# RS_IF.net
KiCad netlist of a schematic drawn in Altium Designer
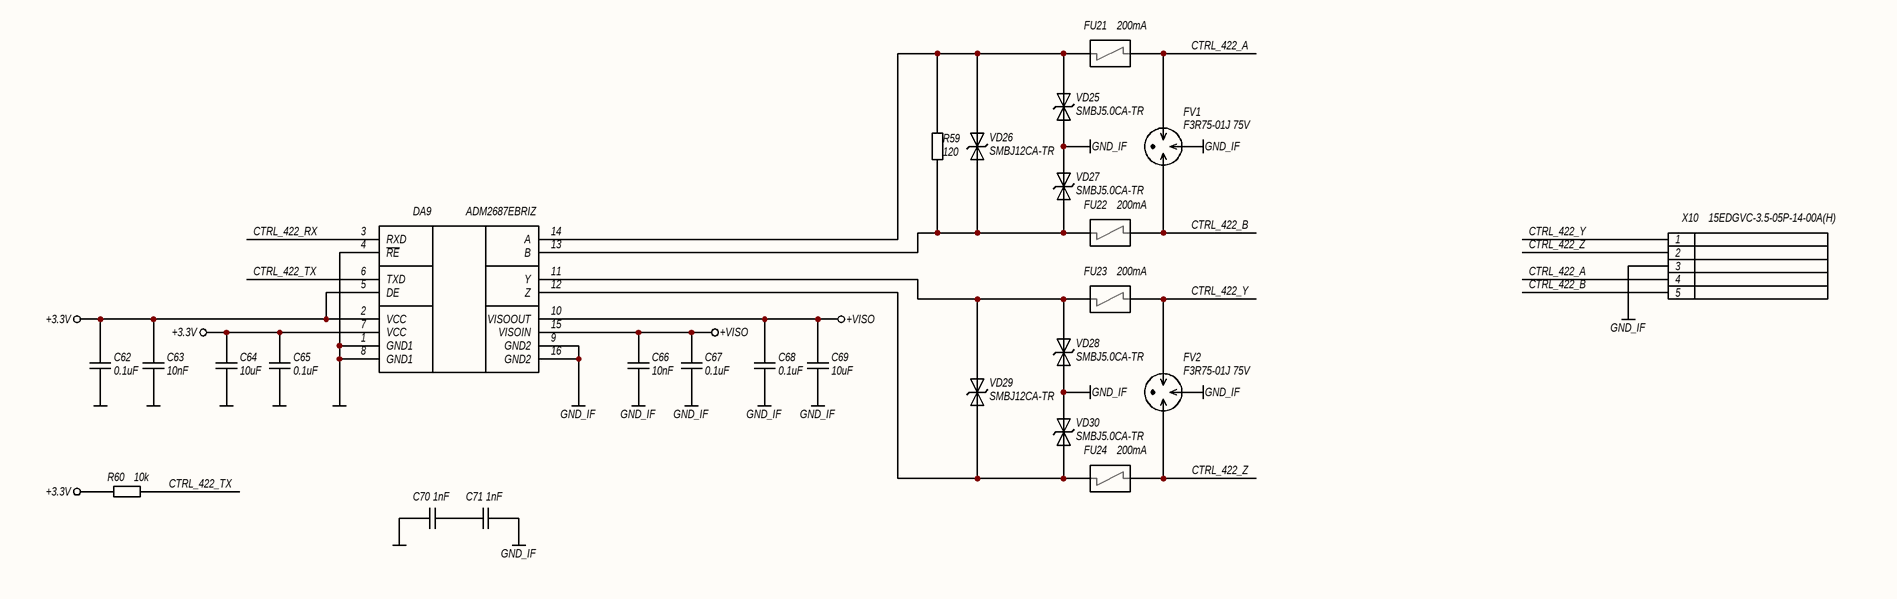
[diagram p0: RS_IF.SchDoc]

(export (version "E")
  (design (tool "Eeschema 10.0.6"))
  (components
    (comp (ref "C62")
      (value "0.1uF")
      (footprint "C0603N")
      (description "Конденсатор")
      (libsource (lib "Components Library") (part "CAP_FIXED"))
    )
    (comp (ref "C63")
      (value "10nF")
      (footprint "C0603N")
      (description "Конденсатор")
      (libsource (lib "Components Library") (part "CAP_FIXED"))
    )
    (comp (ref "C64")
      (value "10uF")
      (footprint "C0805N")
      (description "Конденсатор")
      (libsource (lib "Components Library") (part "CAP_FIXED"))
    )
    (comp (ref "C65")
      (value "0.1uF")
      (footprint "C0603N")
      (description "Конденсатор")
      (libsource (lib "Components Library") (part "CAP_FIXED"))
    )
    (comp (ref "C66")
      (value "10nF")
      (footprint "C0603N")
      (description "Конденсатор")
      (libsource (lib "Components Library") (part "CAP_FIXED"))
    )
    (comp (ref "C67")
      (value "0.1uF")
      (footprint "C0603N")
      (description "Конденсатор")
      (libsource (lib "Components Library") (part "CAP_FIXED"))
    )
    (comp (ref "C68")
      (value "0.1uF")
      (footprint "C0603N")
      (description "Конденсатор")
      (libsource (lib "Components Library") (part "CAP_FIXED"))
    )
    (comp (ref "C69")
      (value "10uF")
      (footprint "C0805N")
      (description "Конденсатор")
      (libsource (lib "Components Library") (part "CAP_FIXED"))
    )
    (comp (ref "C70")
      (value "1nF")
      (footprint "C1808N")
      (description "Конденсатор")
      (libsource (lib "Components Library") (part "CAP_FIXED"))
    )
    (comp (ref "C71")
      (value "1nF")
      (footprint "C1808N")
      (description "Конденсатор")
      (libsource (lib "Components Library") (part "CAP_FIXED"))
    )
    (comp (ref "DA9")
      (value "ADM2687EBRIZ")
      (footprint "SOIC16_IC")
      (description "Микросхема интерфейса RS485")
      (libsource (lib "Components Library") (part "ADM2687E"))
    )
    (comp (ref "FU21")
      (value "200mA")
      (footprint "TBU-CA")
      (description "Полупроводниковый предохранитель")
      (libsource (lib "Components Library") (part "FUSE_TBU"))
    )
    (comp (ref "FU22")
      (value "200mA")
      (footprint "TBU-CA")
      (description "Полупроводниковый предохранитель")
      (libsource (lib "Components Library") (part "FUSE_TBU"))
    )
    (comp (ref "FU23")
      (value "200mA")
      (footprint "TBU-CA")
      (description "Полупроводниковый предохранитель")
      (libsource (lib "Components Library") (part "FUSE_TBU"))
    )
    (comp (ref "FU24")
      (value "200mA")
      (footprint "TBU-CA")
      (description "Полупроводниковый предохранитель")
      (libsource (lib "Components Library") (part "FUSE_TBU"))
    )
    (comp (ref "FV1")
      (value "F3R75-01J 75V")
      (footprint "GDT_3PIN_B2")
      (description "Газовый разрядник, трехвыводный")
      (libsource (lib "Components Library") (part "GDT_3PIN"))
    )
    (comp (ref "FV2")
      (value "F3R75-01J 75V")
      (footprint "GDT_3PIN_B2")
      (description "Газовый разрядник, трехвыводный")
      (libsource (lib "Components Library") (part "GDT_3PIN"))
    )
    (comp (ref "R59")
      (value "120")
      (footprint "R0805N")
      (description "Резистор")
      (libsource (lib "") (part "RES_FIXED_1"))
    )
    (comp (ref "R60")
      (value "10k")
      (footprint "R0603N")
      (description "Резистор")
      (libsource (lib "Components Library") (part "RES_FIXED"))
    )
    (comp (ref "VD25")
      (value "SMBJ5.0CA-TR")
      (footprint "SMB")
      (description "TVS диод двунаправленный")
      (libsource (lib "Components Library") (part "TVS_BIDIR"))
    )
    (comp (ref "VD26")
      (value "SMBJ12CA-TR")
      (footprint "SMB")
      (description "TVS диод двунаправленный")
      (libsource (lib "Components Library") (part "TVS_BIDIR"))
    )
    (comp (ref "VD27")
      (value "SMBJ5.0CA-TR")
      (footprint "SMB")
      (description "TVS диод двунаправленный")
      (libsource (lib "Components Library") (part "TVS_BIDIR"))
    )
    (comp (ref "VD28")
      (value "SMBJ5.0CA-TR")
      (footprint "SMB")
      (description "TVS диод двунаправленный")
      (libsource (lib "Components Library") (part "TVS_BIDIR"))
    )
    (comp (ref "VD29")
      (value "SMBJ12CA-TR")
      (footprint "SMB")
      (description "TVS диод двунаправленный")
      (libsource (lib "Components Library") (part "TVS_BIDIR"))
    )
    (comp (ref "VD30")
      (value "SMBJ5.0CA-TR")
      (footprint "SMB")
      (description "TVS диод двунаправленный")
      (libsource (lib "Components Library") (part "TVS_BIDIR"))
    )
    (comp (ref "X10")
      (value "15EDGVC-3.5-05P-14-00A(H)")
      (footprint "15EDGVC-3.5-05P-14-00A(H)")
      (description "Разъем, 5 контактов")
      (libsource (lib "Components Library") (part "Connector 5"))
    )
  )
  (nets
    (net (code "1") (name "+3.3V") (class "Default")
      (node (ref "C62") (pin "2") (pinfunction "2_2") (pintype "passive"))
      (node (ref "C63") (pin "1") (pinfunction "1_1") (pintype "passive"))
      (node (ref "C64") (pin "2") (pinfunction "2_2") (pintype "passive"))
      (node (ref "C65") (pin "2") (pinfunction "2_2") (pintype "passive"))
      (node (ref "DA9") (pin "2") (pinfunction "VCC_2") (pintype "power_in"))
      (node (ref "DA9") (pin "5") (pinfunction "DE_5") (pintype "power_in"))
      (node (ref "DA9") (pin "7") (pinfunction "VCC_7") (pintype "power_in"))
      (node (ref "R60") (pin "2") (pinfunction "2_2") (pintype "passive"))
    )
    (net (code "2") (name "+VISO") (class "Default")
      (node (ref "C66") (pin "1") (pinfunction "1_1") (pintype "passive"))
      (node (ref "C67") (pin "2") (pinfunction "2_2") (pintype "passive"))
      (node (ref "C68") (pin "2") (pinfunction "2_2") (pintype "passive"))
      (node (ref "C69") (pin "2") (pinfunction "2_2") (pintype "passive"))
      (node (ref "DA9") (pin "10") (pinfunction "VISOOUT_10") (pintype "power_in"))
      (node (ref "DA9") (pin "15") (pinfunction "VISOIN_15") (pintype "power_in"))
    )
    (net (code "3") (name "/CTRL_422_A") (class "Default")
      (node (ref "FU21") (pin "3") (pinfunction "IN/OUT_3") (pintype "passive"))
      (node (ref "FV1") (pin "1") (pinfunction "1_1") (pintype "passive"))
      (node (ref "X10") (pin "4") (pinfunction "4_4") (pintype "power_in"))
    )
    (net (code "4") (name "/CTRL_422_B") (class "Default")
      (node (ref "FU22") (pin "3") (pinfunction "IN/OUT_3") (pintype "passive"))
      (node (ref "FV1") (pin "3") (pinfunction "3_3") (pintype "passive"))
      (node (ref "X10") (pin "5") (pinfunction "5_5") (pintype "power_in"))
    )
    (net (code "5") (name "/CTRL_422_RX") (class "Default")
      (node (ref "DA9") (pin "3") (pinfunction "RXD_3") (pintype "power_in"))
    )
    (net (code "6") (name "/CTRL_422_TX") (class "Default")
      (node (ref "DA9") (pin "6") (pinfunction "TXD_6") (pintype "power_in"))
      (node (ref "R60") (pin "1") (pinfunction "1_1") (pintype "passive"))
    )
    (net (code "7") (name "/CTRL_422_Y") (class "Default")
      (node (ref "FU23") (pin "3") (pinfunction "IN/OUT_3") (pintype "passive"))
      (node (ref "FV2") (pin "1") (pinfunction "1_1") (pintype "passive"))
      (node (ref "X10") (pin "1") (pinfunction "1_1") (pintype "power_in"))
    )
    (net (code "8") (name "/CTRL_422_Z") (class "Default")
      (node (ref "FU24") (pin "3") (pinfunction "IN/OUT_3") (pintype "passive"))
      (node (ref "FV2") (pin "3") (pinfunction "3_3") (pintype "passive"))
      (node (ref "X10") (pin "2") (pinfunction "2_2") (pintype "power_in"))
    )
    (net (code "9") (name "GND") (class "Default")
      (node (ref "C62") (pin "1") (pinfunction "1_1") (pintype "passive"))
      (node (ref "C63") (pin "2") (pinfunction "2_2") (pintype "passive"))
      (node (ref "C64") (pin "1") (pinfunction "1_1") (pintype "passive"))
      (node (ref "C65") (pin "1") (pinfunction "1_1") (pintype "passive"))
      (node (ref "C70") (pin "2") (pinfunction "2_2") (pintype "passive"))
      (node (ref "DA9") (pin "1") (pinfunction "GND1_1") (pintype "power_in"))
      (node (ref "DA9") (pin "4") (pinfunction "~{RE}_4") (pintype "power_in"))
      (node (ref "DA9") (pin "8") (pinfunction "GND1_8") (pintype "power_in"))
    )
    (net (code "10") (name "GND_IF") (class "Default")
      (node (ref "C66") (pin "2") (pinfunction "2_2") (pintype "passive"))
      (node (ref "C67") (pin "1") (pinfunction "1_1") (pintype "passive"))
      (node (ref "C68") (pin "1") (pinfunction "1_1") (pintype "passive"))
      (node (ref "C69") (pin "1") (pinfunction "1_1") (pintype "passive"))
      (node (ref "C71") (pin "1") (pinfunction "1_1") (pintype "passive"))
      (node (ref "DA9") (pin "16") (pinfunction "GND2_16") (pintype "power_in"))
      (node (ref "DA9") (pin "9") (pinfunction "GND2_9") (pintype "power_in"))
      (node (ref "FV1") (pin "2") (pinfunction "2_2") (pintype "passive"))
      (node (ref "FV2") (pin "2") (pinfunction "2_2") (pintype "passive"))
      (node (ref "VD25") (pin "2") (pinfunction "A2_2") (pintype "passive"))
      (node (ref "VD27") (pin "2") (pinfunction "A2_2") (pintype "passive"))
      (node (ref "VD28") (pin "2") (pinfunction "A2_2") (pintype "passive"))
      (node (ref "VD30") (pin "2") (pinfunction "A2_2") (pintype "passive"))
      (node (ref "X10") (pin "3") (pinfunction "3_3") (pintype "power_in"))
    )
    (net (code "11") (name "Net-(C70-Pad1)") (class "Default")
      (node (ref "C70") (pin "1") (pinfunction "1_1") (pintype "passive"))
      (node (ref "C71") (pin "2") (pinfunction "2_2") (pintype "passive"))
    )
    (net (code "12") (name "Net-(DA9-A)") (class "Default")
      (node (ref "DA9") (pin "14") (pinfunction "A_14") (pintype "power_in"))
      (node (ref "FU21") (pin "1") (pinfunction "IN/OUT_1") (pintype "passive"))
      (node (ref "R59") (pin "1") (pinfunction "1_1") (pintype "passive"))
      (node (ref "VD25") (pin "1") (pinfunction "A1_1") (pintype "passive"))
      (node (ref "VD26") (pin "1") (pinfunction "A1_1") (pintype "passive"))
    )
    (net (code "13") (name "Net-(DA9-B)") (class "Default")
      (node (ref "DA9") (pin "13") (pinfunction "B_13") (pintype "power_in"))
      (node (ref "FU22") (pin "1") (pinfunction "IN/OUT_1") (pintype "passive"))
      (node (ref "R59") (pin "2") (pinfunction "2_2") (pintype "passive"))
      (node (ref "VD26") (pin "2") (pinfunction "A2_2") (pintype "passive"))
      (node (ref "VD27") (pin "1") (pinfunction "A1_1") (pintype "passive"))
    )
    (net (code "14") (name "Net-(DA9-Y)") (class "Default")
      (node (ref "DA9") (pin "11") (pinfunction "Y_11") (pintype "power_in"))
      (node (ref "FU23") (pin "1") (pinfunction "IN/OUT_1") (pintype "passive"))
      (node (ref "VD28") (pin "1") (pinfunction "A1_1") (pintype "passive"))
      (node (ref "VD29") (pin "1") (pinfunction "A1_1") (pintype "passive"))
    )
    (net (code "15") (name "Net-(DA9-Z)") (class "Default")
      (node (ref "DA9") (pin "12") (pinfunction "Z_12") (pintype "power_in"))
      (node (ref "FU24") (pin "1") (pinfunction "IN/OUT_1") (pintype "passive"))
      (node (ref "VD29") (pin "2") (pinfunction "A2_2") (pintype "passive"))
      (node (ref "VD30") (pin "1") (pinfunction "A1_1") (pintype "passive"))
    )
  )
)
